# PT100-SensorPCB008.net
KiCad netlist of a schematic drawn in EAGLE
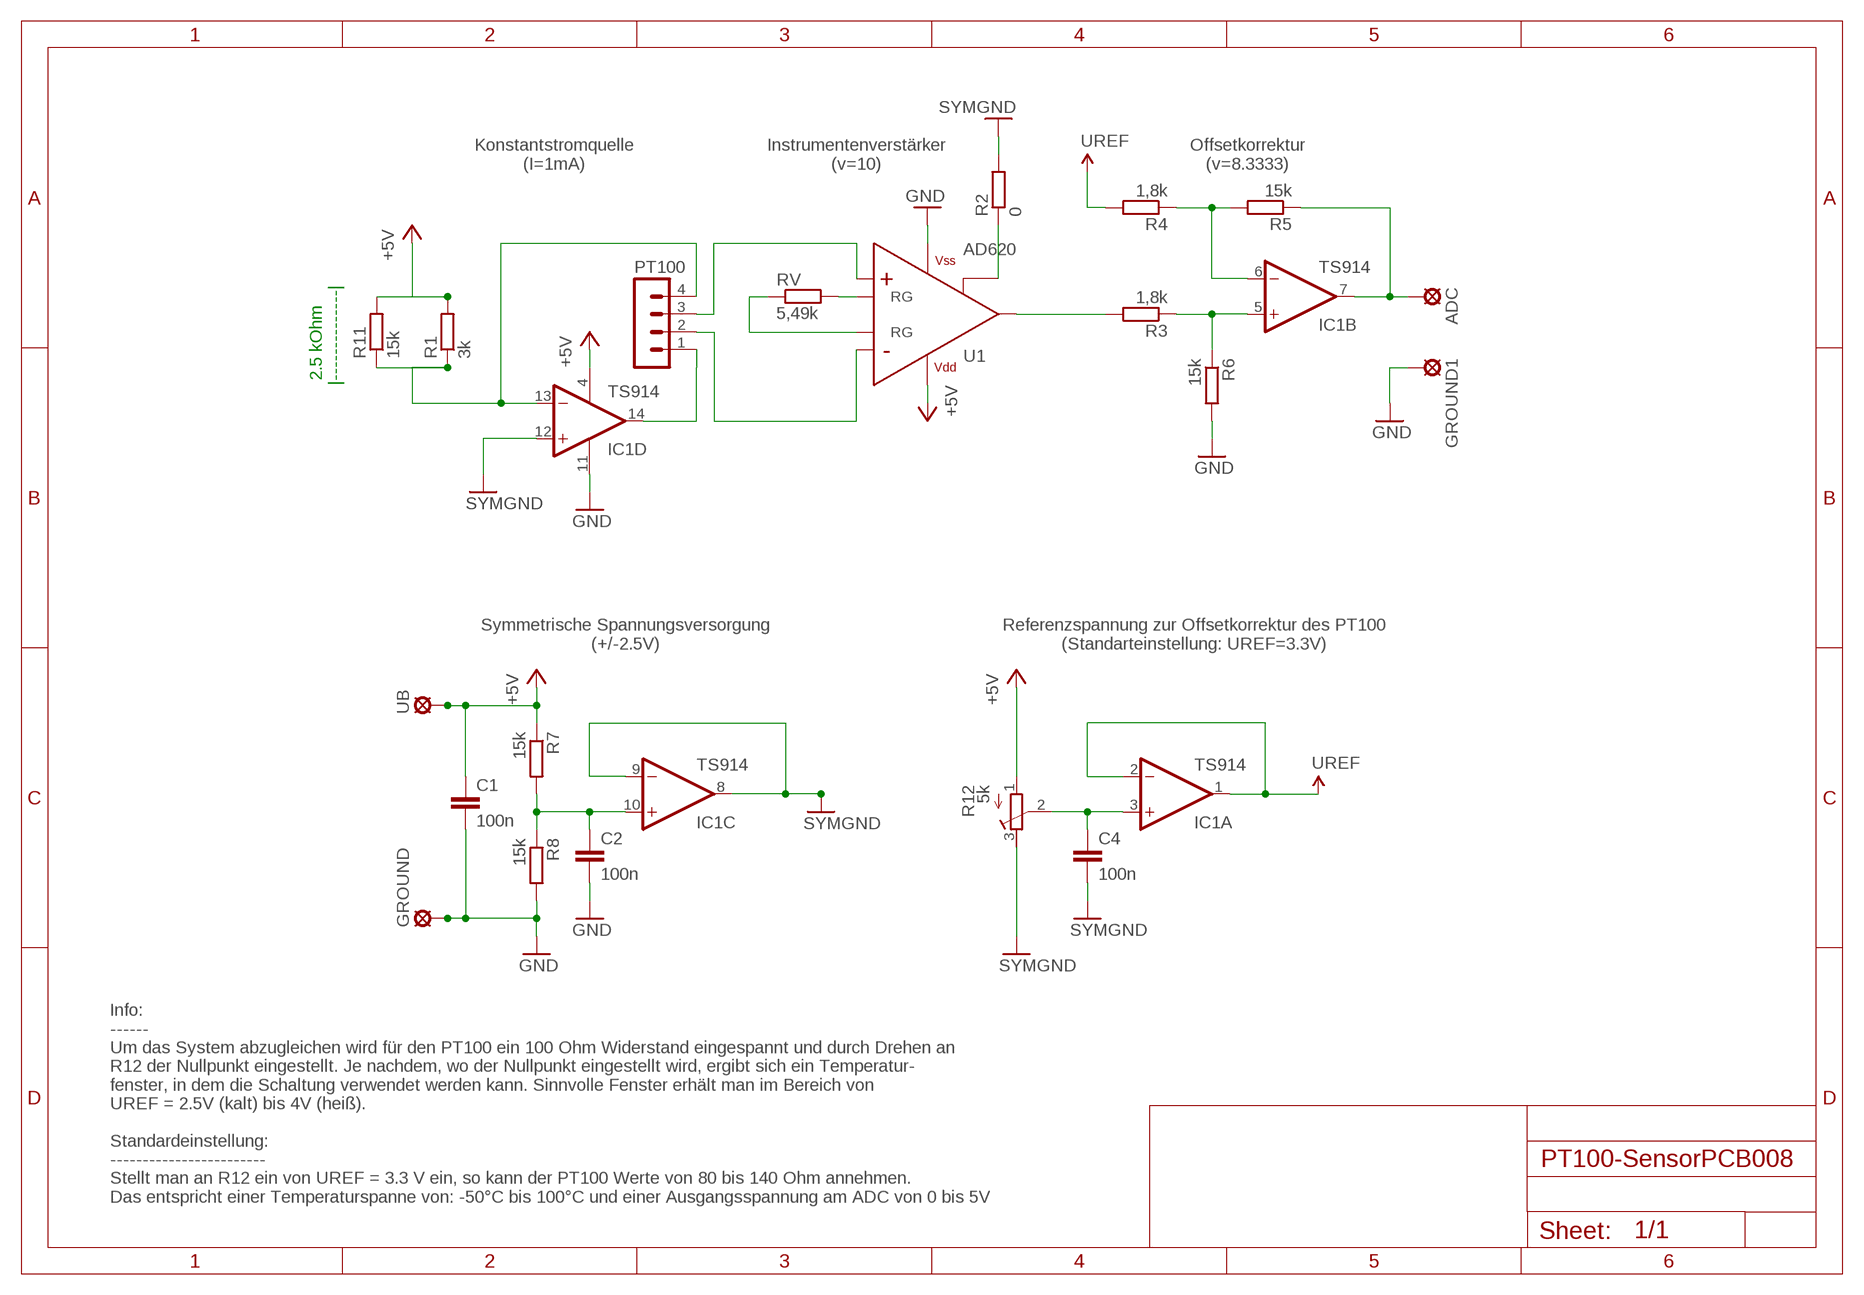
[diagram p0: schematic, sheet 1]

(export (version "E")
  (design (tool "Eeschema 10.0.6"))
  (components
    (comp (ref "ADC")
      (value "LSP10")
      (footprint "eagle-import:LSP10")
      (libsource (lib "eagle-import") (part "LSP10"))
    )
    (comp (ref "C1")
      (value "100n")
      (footprint "eagle-import:C0805")
      (libsource (lib "eagle-import") (part "C-EUC0805"))
    )
    (comp (ref "C2")
      (value "100n")
      (footprint "eagle-import:C0805")
      (libsource (lib "eagle-import") (part "C-EUC0805"))
    )
    (comp (ref "C4")
      (value "100n")
      (footprint "eagle-import:C0805")
      (libsource (lib "eagle-import") (part "C-EUC0805"))
    )
    (comp (ref "GROUND")
      (value "LSP10")
      (footprint "eagle-import:LSP10")
      (libsource (lib "eagle-import") (part "LSP10"))
    )
    (comp (ref "GROUND1")
      (value "LSP10")
      (footprint "eagle-import:LSP10")
      (libsource (lib "eagle-import") (part "LSP10"))
    )
    (comp (ref "IC1")
      (value "TS914")
      (footprint "eagle-import:SO14")
      (libsource (lib "eagle-import") (part "AD8684R"))
    )
    (comp (ref "PT100")
      (value "MA04-1")
      (footprint "eagle-import:MA04-1")
      (libsource (lib "eagle-import") (part "MA04-1"))
    )
    (comp (ref "R1")
      (value "3k")
      (footprint "eagle-import:R0805")
      (libsource (lib "eagle-import") (part "R-EU_R0805"))
    )
    (comp (ref "R2")
      (value "0")
      (footprint "eagle-import:R1206")
      (libsource (lib "eagle-import") (part "R-EU_R1206"))
    )
    (comp (ref "R3")
      (value "1,8k")
      (footprint "eagle-import:R0805")
      (libsource (lib "eagle-import") (part "R-EU_R0805"))
    )
    (comp (ref "R4")
      (value "1,8k")
      (footprint "eagle-import:R0805")
      (libsource (lib "eagle-import") (part "R-EU_R0805"))
    )
    (comp (ref "R5")
      (value "15k")
      (footprint "eagle-import:R0805")
      (libsource (lib "eagle-import") (part "R-EU_R0805"))
    )
    (comp (ref "R6")
      (value "15k")
      (footprint "eagle-import:R0805")
      (libsource (lib "eagle-import") (part "R-EU_R0805"))
    )
    (comp (ref "R7")
      (value "15k")
      (footprint "eagle-import:R0805")
      (libsource (lib "eagle-import") (part "R-EU_R0805"))
    )
    (comp (ref "R8")
      (value "15k")
      (footprint "eagle-import:R0805")
      (libsource (lib "eagle-import") (part "R-EU_R0805"))
    )
    (comp (ref "R11")
      (value "15k")
      (footprint "eagle-import:R0805")
      (libsource (lib "eagle-import") (part "R-EU_R0805"))
    )
    (comp (ref "R12")
      (value "5k")
      (footprint "eagle-import:RTRIM3374")
      (libsource (lib "eagle-import") (part "R-TRIMM3374"))
    )
    (comp (ref "RV")
      (value "5,49k")
      (footprint "eagle-import:0207_2V")
      (libsource (lib "eagle-import") (part "resistor_R-EU_0207/2V"))
    )
    (comp (ref "U1")
      (value "AD620")
      (footprint "eagle-import:SO08-TIGHT")
      (libsource (lib "eagle-import") (part "AD627SOIC"))
    )
    (comp (ref "UB")
      (value "LSP10")
      (footprint "eagle-import:LSP10")
      (libsource (lib "eagle-import") (part "LSP10"))
    )
  )
  (nets
    (net (code "1") (name "+5V") (class "Default")
      (node (ref "C1") (pin "1") (pinfunction "1_1") (pintype "passive"))
      (node (ref "IC1") (pin "4") (pinfunction "V+_4") (pintype "power_in"))
      (node (ref "R1") (pin "2") (pinfunction "2_2") (pintype "passive"))
      (node (ref "R11") (pin "2") (pinfunction "2_2") (pintype "passive"))
      (node (ref "R12") (pin "1") (pinfunction "A_1") (pintype "passive"))
      (node (ref "R7") (pin "1") (pinfunction "1_1") (pintype "passive"))
      (node (ref "U1") (pin "7") (pinfunction "VS+_7") (pintype "bidirectional"))
      (node (ref "UB") (pin "MP") (pinfunction "MP_MP") (pintype "passive"))
    )
    (net (code "2") (name "GND") (class "Default")
      (node (ref "C1") (pin "2") (pinfunction "2_2") (pintype "passive"))
      (node (ref "C2") (pin "2") (pinfunction "2_2") (pintype "passive"))
      (node (ref "GROUND") (pin "MP") (pinfunction "MP_MP") (pintype "passive"))
      (node (ref "GROUND1") (pin "MP") (pinfunction "MP_MP") (pintype "passive"))
      (node (ref "IC1") (pin "11") (pinfunction "V-_11") (pintype "power_in"))
      (node (ref "R6") (pin "2") (pinfunction "2_2") (pintype "passive"))
      (node (ref "R8") (pin "2") (pinfunction "2_2") (pintype "passive"))
      (node (ref "U1") (pin "4") (pinfunction "VS-_4") (pintype "bidirectional"))
    )
    (net (code "3") (name "Net-(IC1A-+IN)") (class "Default")
      (node (ref "C4") (pin "1") (pinfunction "1_1") (pintype "passive"))
      (node (ref "IC1") (pin "3") (pinfunction "+IN_3") (pintype "input"))
      (node (ref "R12") (pin "2") (pinfunction "S_2") (pintype "passive"))
    )
    (net (code "4") (name "Net-(IC1B-+IN)") (class "Default")
      (node (ref "IC1") (pin "5") (pinfunction "+IN_5") (pintype "input"))
      (node (ref "R3") (pin "1") (pinfunction "1_1") (pintype "passive"))
      (node (ref "R6") (pin "1") (pinfunction "1_1") (pintype "passive"))
    )
    (net (code "5") (name "Net-(IC1B--IN)") (class "Default")
      (node (ref "IC1") (pin "6") (pinfunction "-IN_6") (pintype "input"))
      (node (ref "R4") (pin "1") (pinfunction "1_1") (pintype "passive"))
      (node (ref "R5") (pin "2") (pinfunction "2_2") (pintype "passive"))
    )
    (net (code "6") (name "Net-(IC1B-OUT)") (class "Default")
      (node (ref "ADC") (pin "MP") (pinfunction "MP_MP") (pintype "passive"))
      (node (ref "IC1") (pin "7") (pinfunction "OUT_7") (pintype "output"))
      (node (ref "R5") (pin "1") (pinfunction "1_1") (pintype "passive"))
    )
    (net (code "7") (name "Net-(IC1C-+IN)") (class "Default")
      (node (ref "C2") (pin "1") (pinfunction "1_1") (pintype "passive"))
      (node (ref "IC1") (pin "10") (pinfunction "+IN_10") (pintype "input"))
      (node (ref "R7") (pin "2") (pinfunction "2_2") (pintype "passive"))
      (node (ref "R8") (pin "1") (pinfunction "1_1") (pintype "passive"))
    )
    (net (code "8") (name "Net-(IC1D--IN)") (class "Default")
      (node (ref "IC1") (pin "13") (pinfunction "-IN_13") (pintype "input"))
      (node (ref "PT100") (pin "4") (pinfunction "4_4") (pintype "passive"))
      (node (ref "R1") (pin "1") (pinfunction "1_1") (pintype "passive"))
      (node (ref "R11") (pin "1") (pinfunction "1_1") (pintype "passive"))
    )
    (net (code "9") (name "Net-(IC1D-OUT)") (class "Default")
      (node (ref "IC1") (pin "14") (pinfunction "OUT_14") (pintype "output"))
      (node (ref "PT100") (pin "1") (pinfunction "1_1") (pintype "passive"))
    )
    (net (code "10") (name "Net-(RV-Pad1)") (class "Default")
      (node (ref "RV") (pin "1") (pinfunction "1_1") (pintype "passive"))
      (node (ref "U1") (pin "1") (pinfunction "RG_1") (pintype "bidirectional"))
    )
    (net (code "11") (name "Net-(RV-Pad2)") (class "Default")
      (node (ref "RV") (pin "2") (pinfunction "2_2") (pintype "passive"))
      (node (ref "U1") (pin "8") (pinfunction "RG_8") (pintype "bidirectional"))
    )
    (net (code "12") (name "Net-(U1-IN+)") (class "Default")
      (node (ref "PT100") (pin "3") (pinfunction "3_3") (pintype "passive"))
      (node (ref "U1") (pin "3") (pinfunction "IN+_3") (pintype "bidirectional"))
    )
    (net (code "13") (name "Net-(U1-IN-)") (class "Default")
      (node (ref "PT100") (pin "2") (pinfunction "2_2") (pintype "passive"))
      (node (ref "U1") (pin "2") (pinfunction "IN-_2") (pintype "bidirectional"))
    )
    (net (code "14") (name "Net-(U1-OUTPUT)") (class "Default")
      (node (ref "R3") (pin "2") (pinfunction "2_2") (pintype "passive"))
      (node (ref "U1") (pin "6") (pinfunction "OUTPUT_6") (pintype "bidirectional"))
    )
    (net (code "15") (name "Net-(U1-REF)") (class "Default")
      (node (ref "R2") (pin "1") (pinfunction "1_1") (pintype "passive"))
      (node (ref "U1") (pin "5") (pinfunction "REF_5") (pintype "bidirectional"))
    )
    (net (code "16") (name "SYMGND") (class "Default")
      (node (ref "C4") (pin "2") (pinfunction "2_2") (pintype "passive"))
      (node (ref "IC1") (pin "12") (pinfunction "+IN_12") (pintype "input"))
      (node (ref "IC1") (pin "8") (pinfunction "OUT_8") (pintype "output"))
      (node (ref "IC1") (pin "9") (pinfunction "-IN_9") (pintype "input"))
      (node (ref "R12") (pin "3") (pinfunction "E_3") (pintype "passive"))
      (node (ref "R2") (pin "2") (pinfunction "2_2") (pintype "passive"))
    )
    (net (code "17") (name "UREF") (class "Default")
      (node (ref "IC1") (pin "1") (pinfunction "OUT_1") (pintype "output"))
      (node (ref "IC1") (pin "2") (pinfunction "-IN_2") (pintype "input"))
      (node (ref "R4") (pin "2") (pinfunction "2_2") (pintype "passive"))
    )
  )
)
